# Herradura.net
KiCad netlist of a schematic drawn in Altium Designer
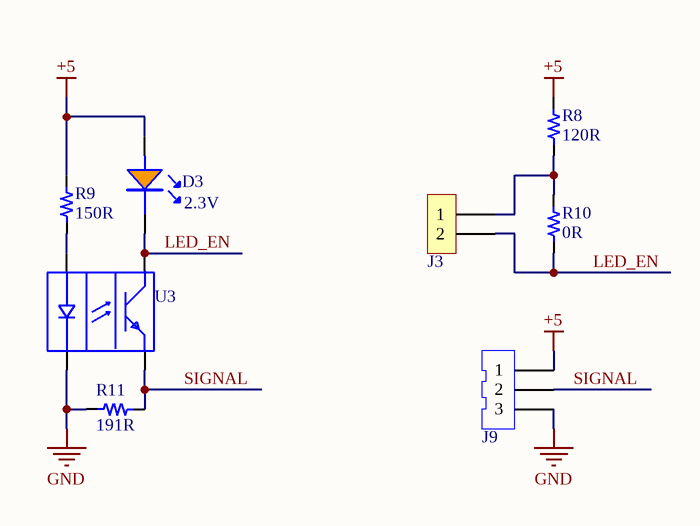
[diagram p0: Herradura.SchDoc]

(export (version "E")
  (design (tool "Eeschema 10.0.6"))
  (components
    (comp (ref "D3")
      (value "2.3V")
      (footprint "0805_LED")
      (description "LED ORANGE WATER CLEAR 0805 SMD")
      (fields
        (field (name "MANUFACTURER") "XINGLIGHT")
        (field (name "MANUFACTURER PART NUMBER") "XL-2012UOC")
      )
      (libsource (lib "CNCLib") (part "LED_0805_Orange"))
    )
    (comp (ref "J3")
      (value "2x1")
      (footprint "H_2x1_TH_100mil")
      (description "H_Male_2x1_TH_100mil")
      (libsource (lib "CNCLib") (part "H_Male_2x1_TH_100mil"))
    )
    (comp (ref "J9")
      (value "CONN HEADER TH 3POS 2.5mm")
      (fields
        (field (name "MANUFACTURER") "JST")
        (field (name "MANUFACTURER PART NUMBER") "B3B-XH-A(LF)(SN)")
      )
      (libsource (lib "CNCLib") (part "Connector JST 3pin"))
    )
    (comp (ref "R8")
      (value "120R")
      (footprint "0603_res")
      (description "100mW Thick Film Resistor 75V ±100ppm/℃ ±1% 120Ω 0603 Chip Resistor - Surface Mount ROHS")
      (fields
        (field (name "MANUFACTURER") "FOJAN")
        (field (name "MANUFACTURER PART NUMBER") "FRC0603F1200TS")
      )
      (libsource (lib "CNCLib") (part "Res_120R_0603_1/10W"))
    )
    (comp (ref "R9")
      (value "150R")
      (footprint "0603_res")
      (description "100mW Thick Film Resistor 75V ±100ppm/℃ ±1% 150Ω 0603 Chip Resistor - Surface Mount ROHS")
      (fields (field (name "MANUFACTURER") "RALEC") (field (name "MANUFACTURER PART NUMBER") "RTT031500FTP"))
      (libsource (lib "CNCLib") (part "Res_150R_0603_1/10W"))
    )
    (comp (ref "R10")
      (value "0R")
      (footprint "0603_res")
      (description "RES SMD 0R OHM 5% 1/10W 0603")
      (fields
        (field (name "MANUFACTURER") "FOJAN")
        (field (name "MANUFACTURER PART NUMBER") "FRC0603P000 TS")
      )
      (libsource (lib "CNCLib") (part "Res_0R_0603_1/10W"))
    )
    (comp (ref "R11")
      (value "191R")
      (footprint "0603_res")
      (description "100mW Thick Film Resistor 75V ±100ppm/℃ ±1% 191Ω 0603 Chip Resistor - Surface Mount ROHS")
      (fields
        (field (name "MANUFACTURER") "FOJAN")
        (field (name "MANUFACTURER PART NUMBER") "FRC0603F1910TS")
      )
      (libsource (lib "CNCLib") (part "Res_191R_0603_1/10W"))
    )
    (comp (ref "U3")
      (value "SENSOR OPT SLOT PHOTOTRAN PCB MT")
      (footprint "RES_0402")
      (description "850nm 1.4V DIP-4 Photointerrupters - Slot Type - Transistor Output RoHS")
      (fields (field (name "MANUFACTURER") "ROHM") (field (name "MANUFACTURER PART NUMBER") "RPI-441C1E"))
      (libsource (lib "CNCLib") (part "RPI-441C1E"))
    )
  )
  (nets
    (net (code "1") (name "+5") (class "Default")
      (node (ref "D3") (pin "1") (pinfunction "A_1") (pintype "passive"))
      (node (ref "J9") (pin "1") (pinfunction "1_1") (pintype "passive"))
      (node (ref "R8") (pin "2") (pinfunction "2_2") (pintype "passive"))
      (node (ref "R9") (pin "2") (pinfunction "2_2") (pintype "passive"))
    )
    (net (code "2") (name "/LED_EN") (class "Default")
      (node (ref "D3") (pin "2") (pinfunction "2_2") (pintype "passive"))
      (node (ref "J3") (pin "2") (pinfunction "2_2") (pintype "passive"))
      (node (ref "R10") (pin "1") (pinfunction "1_1") (pintype "passive"))
      (node (ref "U3") (pin "3") (pinfunction "COLLECTOR_3") (pintype "passive"))
    )
    (net (code "3") (name "/SIGNAL") (class "Default")
      (node (ref "J9") (pin "2") (pinfunction "2_2") (pintype "passive"))
      (node (ref "R11") (pin "2") (pinfunction "2_2") (pintype "passive"))
      (node (ref "U3") (pin "4") (pinfunction "EMISOR_4") (pintype "passive"))
    )
    (net (code "4") (name "GND") (class "Default")
      (node (ref "J9") (pin "3") (pinfunction "3_3") (pintype "passive"))
      (node (ref "R11") (pin "1") (pinfunction "1_1") (pintype "passive"))
      (node (ref "U3") (pin "1") (pinfunction "CATHODE_1") (pintype "passive"))
    )
    (net (code "5") (name "Net-(J3-Pad1)") (class "Default")
      (node (ref "J3") (pin "1") (pinfunction "1_1") (pintype "passive"))
      (node (ref "R10") (pin "2") (pinfunction "2_2") (pintype "passive"))
      (node (ref "R8") (pin "1") (pinfunction "1_1") (pintype "passive"))
    )
    (net (code "6") (name "Net-(U3-ANODE)") (class "Default")
      (node (ref "R9") (pin "1") (pinfunction "1_1") (pintype "passive"))
      (node (ref "U3") (pin "2") (pinfunction "ANODE_2") (pintype "passive"))
    )
  )
)
